# ESP32_adapter_revA.net
KiCad netlist of a schematic drawn in EAGLE
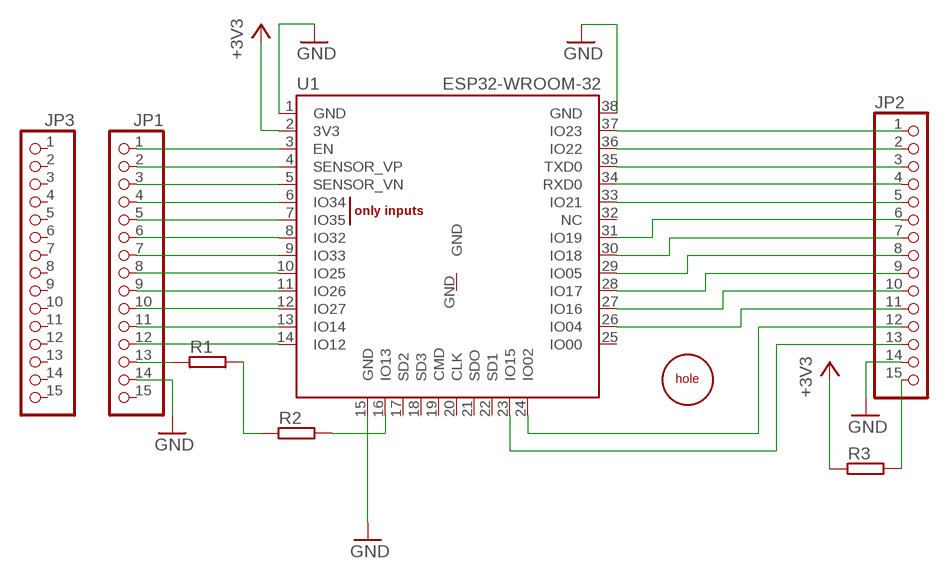
[diagram p0: schematic, sheet 1]

(export (version "E")
  (design (tool "Eeschema 10.0.6"))
  (components
    (comp (ref "JP1")
      (value "PINHD-1X15")
      (footprint "eagle-import:1X15")
      (libsource (lib "eagle-import") (part "PINHD-1X15"))
    )
    (comp (ref "JP2")
      (value "PINHD-1X15")
      (footprint "eagle-import:1X15")
      (libsource (lib "eagle-import") (part "PINHD-1X15"))
    )
    (comp (ref "JP3")
      (value "PINHD-1X15")
      (footprint "eagle-import:1X15")
      (libsource (lib "eagle-import") (part "PINHD-1X15"))
    )
    (comp (ref "R1")
      (value "R'2'")
      (footprint "eagle-import:R0805")
      (libsource (lib "eagle-import") (part "R'2'"))
    )
    (comp (ref "R2")
      (value "R'2'")
      (footprint "eagle-import:R0805")
      (libsource (lib "eagle-import") (part "R'2'"))
    )
    (comp (ref "R3")
      (value "R'2'")
      (footprint "eagle-import:R0805")
      (libsource (lib "eagle-import") (part "R'2'"))
    )
    (comp (ref "U$1")
      (value "HOLE")
      (footprint "eagle-import:HOLE")
      (libsource (lib "eagle-import") (part "HOLE"))
    )
    (comp (ref "U1")
      (value "ESP-WROOM-32")
      (footprint "eagle-import:ESP-WROOM-32")
      (libsource (lib "eagle-import") (part "ESP-WROOM-32"))
    )
  )
  (nets
    (net (code "1") (name "+3V3") (class "Default")
      (node (ref "R3") (pin "1") (pinfunction "P$1_1") (pintype "bidirectional"))
      (node (ref "U1") (pin "2") (pinfunction "3V3_2") (pintype "bidirectional"))
    )
    (net (code "2") (name "GND") (class "Default")
      (node (ref "JP1") (pin "14") (pinfunction "14_14") (pintype "passive"))
      (node (ref "JP2") (pin "14") (pinfunction "14_14") (pintype "passive"))
      (node (ref "U1") (pin "1") (pinfunction "GND_1") (pintype "bidirectional"))
      (node (ref "U1") (pin "15") (pinfunction "GND_15") (pintype "bidirectional"))
      (node (ref "U1") (pin "38") (pinfunction "GND_38") (pintype "bidirectional"))
    )
    (net (code "3") (name "Net-(R1-P$1)") (class "Default")
      (node (ref "JP1") (pin "13") (pinfunction "13_13") (pintype "passive"))
      (node (ref "R1") (pin "1") (pinfunction "P$1_1") (pintype "bidirectional"))
    )
    (net (code "4") (name "Net-(R1-P$2)") (class "Default")
      (node (ref "R1") (pin "2") (pinfunction "P$2_2") (pintype "bidirectional"))
      (node (ref "R2") (pin "1") (pinfunction "P$1_1") (pintype "bidirectional"))
    )
    (net (code "5") (name "Net-(R2-P$2)") (class "Default")
      (node (ref "R2") (pin "2") (pinfunction "P$2_2") (pintype "bidirectional"))
      (node (ref "U1") (pin "16") (pinfunction "IO13_16") (pintype "bidirectional"))
    )
    (net (code "6") (name "Net-(R3-P$2)") (class "Default")
      (node (ref "JP2") (pin "15") (pinfunction "15_15") (pintype "passive"))
      (node (ref "R3") (pin "2") (pinfunction "P$2_2") (pintype "bidirectional"))
    )
    (net (code "7") (name "Net-(U1-EN)") (class "Default")
      (node (ref "JP1") (pin "1") (pinfunction "1_1") (pintype "passive"))
      (node (ref "U1") (pin "3") (pinfunction "EN_3") (pintype "bidirectional"))
    )
    (net (code "8") (name "Net-(U1-IO02)") (class "Default")
      (node (ref "JP2") (pin "12") (pinfunction "12_12") (pintype "passive"))
      (node (ref "U1") (pin "24") (pinfunction "IO02_24") (pintype "bidirectional"))
    )
    (net (code "9") (name "Net-(U1-IO04)") (class "Default")
      (node (ref "JP2") (pin "11") (pinfunction "11_11") (pintype "passive"))
      (node (ref "U1") (pin "26") (pinfunction "IO04_26") (pintype "bidirectional"))
    )
    (net (code "10") (name "Net-(U1-IO05)") (class "Default")
      (node (ref "JP2") (pin "8") (pinfunction "8_8") (pintype "passive"))
      (node (ref "U1") (pin "29") (pinfunction "IO05_29") (pintype "bidirectional"))
    )
    (net (code "11") (name "Net-(U1-IO12)") (class "Default")
      (node (ref "JP1") (pin "12") (pinfunction "12_12") (pintype "passive"))
      (node (ref "U1") (pin "14") (pinfunction "IO12_14") (pintype "bidirectional"))
    )
    (net (code "12") (name "Net-(U1-IO14)") (class "Default")
      (node (ref "JP1") (pin "11") (pinfunction "11_11") (pintype "passive"))
      (node (ref "U1") (pin "13") (pinfunction "IO14_13") (pintype "bidirectional"))
    )
    (net (code "13") (name "Net-(U1-IO15)") (class "Default")
      (node (ref "JP2") (pin "13") (pinfunction "13_13") (pintype "passive"))
      (node (ref "U1") (pin "23") (pinfunction "IO15_23") (pintype "bidirectional"))
    )
    (net (code "14") (name "Net-(U1-IO16)") (class "Default")
      (node (ref "JP2") (pin "10") (pinfunction "10_10") (pintype "passive"))
      (node (ref "U1") (pin "27") (pinfunction "IO16_27") (pintype "bidirectional"))
    )
    (net (code "15") (name "Net-(U1-IO17)") (class "Default")
      (node (ref "JP2") (pin "9") (pinfunction "9_9") (pintype "passive"))
      (node (ref "U1") (pin "28") (pinfunction "IO17_28") (pintype "bidirectional"))
    )
    (net (code "16") (name "Net-(U1-IO18)") (class "Default")
      (node (ref "JP2") (pin "7") (pinfunction "7_7") (pintype "passive"))
      (node (ref "U1") (pin "30") (pinfunction "IO18_30") (pintype "bidirectional"))
    )
    (net (code "17") (name "Net-(U1-IO19)") (class "Default")
      (node (ref "JP2") (pin "6") (pinfunction "6_6") (pintype "passive"))
      (node (ref "U1") (pin "31") (pinfunction "IO19_31") (pintype "bidirectional"))
    )
    (net (code "18") (name "Net-(U1-IO21)") (class "Default")
      (node (ref "JP2") (pin "5") (pinfunction "5_5") (pintype "passive"))
      (node (ref "U1") (pin "33") (pinfunction "IO21_33") (pintype "bidirectional"))
    )
    (net (code "19") (name "Net-(U1-IO22)") (class "Default")
      (node (ref "JP2") (pin "2") (pinfunction "2_2") (pintype "passive"))
      (node (ref "U1") (pin "36") (pinfunction "IO22_36") (pintype "bidirectional"))
    )
    (net (code "20") (name "Net-(U1-IO23)") (class "Default")
      (node (ref "JP2") (pin "1") (pinfunction "1_1") (pintype "passive"))
      (node (ref "U1") (pin "37") (pinfunction "IO23_37") (pintype "bidirectional"))
    )
    (net (code "21") (name "Net-(U1-IO25)") (class "Default")
      (node (ref "JP1") (pin "8") (pinfunction "8_8") (pintype "passive"))
      (node (ref "U1") (pin "10") (pinfunction "IO25_10") (pintype "bidirectional"))
    )
    (net (code "22") (name "Net-(U1-IO26)") (class "Default")
      (node (ref "JP1") (pin "9") (pinfunction "9_9") (pintype "passive"))
      (node (ref "U1") (pin "11") (pinfunction "IO26_11") (pintype "bidirectional"))
    )
    (net (code "23") (name "Net-(U1-IO27)") (class "Default")
      (node (ref "JP1") (pin "10") (pinfunction "10_10") (pintype "passive"))
      (node (ref "U1") (pin "12") (pinfunction "IO27_12") (pintype "bidirectional"))
    )
    (net (code "24") (name "Net-(U1-IO32)") (class "Default")
      (node (ref "JP1") (pin "6") (pinfunction "6_6") (pintype "passive"))
      (node (ref "U1") (pin "8") (pinfunction "IO32_8") (pintype "bidirectional"))
    )
    (net (code "25") (name "Net-(U1-IO33)") (class "Default")
      (node (ref "JP1") (pin "7") (pinfunction "7_7") (pintype "passive"))
      (node (ref "U1") (pin "9") (pinfunction "IO33_9") (pintype "bidirectional"))
    )
    (net (code "26") (name "Net-(U1-IO34)") (class "Default")
      (node (ref "JP1") (pin "4") (pinfunction "4_4") (pintype "passive"))
      (node (ref "U1") (pin "6") (pinfunction "IO34_6") (pintype "input"))
    )
    (net (code "27") (name "Net-(U1-IO35)") (class "Default")
      (node (ref "JP1") (pin "5") (pinfunction "5_5") (pintype "passive"))
      (node (ref "U1") (pin "7") (pinfunction "IO35_7") (pintype "input"))
    )
    (net (code "28") (name "Net-(U1-RXD0)") (class "Default")
      (node (ref "JP2") (pin "4") (pinfunction "4_4") (pintype "passive"))
      (node (ref "U1") (pin "34") (pinfunction "RXD0_34") (pintype "bidirectional"))
    )
    (net (code "29") (name "Net-(U1-SENSOR_VN)") (class "Default")
      (node (ref "JP1") (pin "3") (pinfunction "3_3") (pintype "passive"))
      (node (ref "U1") (pin "5") (pinfunction "SENSOR_VN_5") (pintype "input"))
    )
    (net (code "30") (name "Net-(U1-SENSOR_VP)") (class "Default")
      (node (ref "JP1") (pin "2") (pinfunction "2_2") (pintype "passive"))
      (node (ref "U1") (pin "4") (pinfunction "SENSOR_VP_4") (pintype "input"))
    )
    (net (code "31") (name "Net-(U1-TXD0)") (class "Default")
      (node (ref "JP2") (pin "3") (pinfunction "3_3") (pintype "passive"))
      (node (ref "U1") (pin "35") (pinfunction "TXD0_35") (pintype "bidirectional"))
    )
    (net (code "32") (name "unconnected-(JP1-Pad15)") (class "Default")
      (node (ref "JP1") (pin "15") (pinfunction "15_15") (pintype "passive"))
    )
    (net (code "33") (name "unconnected-(JP3-Pad1)") (class "Default")
      (node (ref "JP3") (pin "1") (pinfunction "1_1") (pintype "passive"))
    )
    (net (code "34") (name "unconnected-(JP3-Pad2)") (class "Default")
      (node (ref "JP3") (pin "2") (pinfunction "2_2") (pintype "passive"))
    )
    (net (code "35") (name "unconnected-(JP3-Pad3)") (class "Default")
      (node (ref "JP3") (pin "3") (pinfunction "3_3") (pintype "passive"))
    )
    (net (code "36") (name "unconnected-(JP3-Pad4)") (class "Default")
      (node (ref "JP3") (pin "4") (pinfunction "4_4") (pintype "passive"))
    )
    (net (code "37") (name "unconnected-(JP3-Pad5)") (class "Default")
      (node (ref "JP3") (pin "5") (pinfunction "5_5") (pintype "passive"))
    )
    (net (code "38") (name "unconnected-(JP3-Pad6)") (class "Default")
      (node (ref "JP3") (pin "6") (pinfunction "6_6") (pintype "passive"))
    )
    (net (code "39") (name "unconnected-(JP3-Pad7)") (class "Default")
      (node (ref "JP3") (pin "7") (pinfunction "7_7") (pintype "passive"))
    )
    (net (code "40") (name "unconnected-(JP3-Pad8)") (class "Default")
      (node (ref "JP3") (pin "8") (pinfunction "8_8") (pintype "passive"))
    )
    (net (code "41") (name "unconnected-(JP3-Pad9)") (class "Default")
      (node (ref "JP3") (pin "9") (pinfunction "9_9") (pintype "passive"))
    )
    (net (code "42") (name "unconnected-(JP3-Pad10)") (class "Default")
      (node (ref "JP3") (pin "10") (pinfunction "10_10") (pintype "passive"))
    )
    (net (code "43") (name "unconnected-(JP3-Pad11)") (class "Default")
      (node (ref "JP3") (pin "11") (pinfunction "11_11") (pintype "passive"))
    )
    (net (code "44") (name "unconnected-(JP3-Pad12)") (class "Default")
      (node (ref "JP3") (pin "12") (pinfunction "12_12") (pintype "passive"))
    )
    (net (code "45") (name "unconnected-(JP3-Pad13)") (class "Default")
      (node (ref "JP3") (pin "13") (pinfunction "13_13") (pintype "passive"))
    )
    (net (code "46") (name "unconnected-(JP3-Pad14)") (class "Default")
      (node (ref "JP3") (pin "14") (pinfunction "14_14") (pintype "passive"))
    )
    (net (code "47") (name "unconnected-(JP3-Pad15)") (class "Default")
      (node (ref "JP3") (pin "15") (pinfunction "15_15") (pintype "passive"))
    )
    (net (code "48") (name "unconnected-(U1-CLK-Pad20)") (class "Default")
      (node (ref "U1") (pin "20") (pinfunction "CLK_20") (pintype "bidirectional"))
    )
    (net (code "49") (name "unconnected-(U1-CMD-Pad19)") (class "Default")
      (node (ref "U1") (pin "19") (pinfunction "CMD_19") (pintype "bidirectional"))
    )
    (net (code "50") (name "unconnected-(U1-IO00-Pad25)") (class "Default")
      (node (ref "U1") (pin "25") (pinfunction "IO00_25") (pintype "bidirectional"))
    )
    (net (code "51") (name "unconnected-(U1-NC-Pad32)") (class "Default")
      (node (ref "U1") (pin "32") (pinfunction "NC_32") (pintype "bidirectional"))
    )
    (net (code "52") (name "unconnected-(U1-PadGND)") (class "Default")
      (node (ref "U1") (pin "GND") (pinfunction "GND_GND") (pintype "bidirectional"))
    )
    (net (code "53") (name "unconnected-(U1-SD1-Pad22)") (class "Default")
      (node (ref "U1") (pin "22") (pinfunction "SD1_22") (pintype "bidirectional"))
    )
    (net (code "54") (name "unconnected-(U1-SD2-Pad17)") (class "Default")
      (node (ref "U1") (pin "17") (pinfunction "SD2_17") (pintype "bidirectional"))
    )
    (net (code "55") (name "unconnected-(U1-SD3-Pad18)") (class "Default")
      (node (ref "U1") (pin "18") (pinfunction "SD3_18") (pintype "bidirectional"))
    )
    (net (code "56") (name "unconnected-(U1-SDO-Pad21)") (class "Default")
      (node (ref "U1") (pin "21") (pinfunction "SDO_21") (pintype "bidirectional"))
    )
  )
)
